# module_RF69.net
KiCad netlist of a schematic drawn in EAGLE
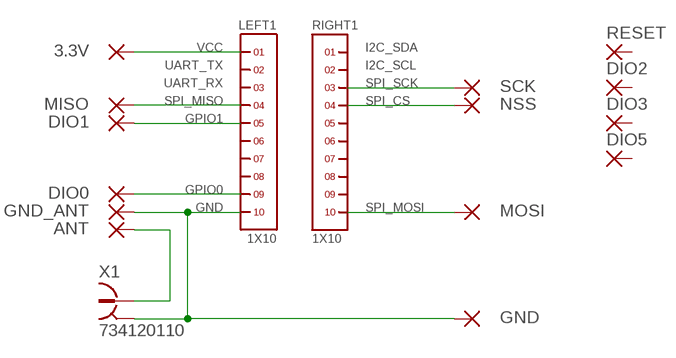
[diagram p0: schematic, sheet 1]

(export (version "E")
  (design (tool "Eeschema 10.0.6"))
  (components
    (comp (ref "3.3V")
      (value "SMD2")
      (footprint "eagle-import:SMD1,27-2,54")
      (libsource (lib "eagle-import") (part "SMD2"))
    )
    (comp (ref "ANT")
      (value "SMD2")
      (footprint "eagle-import:SMD1,27-2,54")
      (libsource (lib "eagle-import") (part "SMD2"))
    )
    (comp (ref "DIO0")
      (value "SMD2")
      (footprint "eagle-import:SMD1,27-2,54")
      (libsource (lib "eagle-import") (part "SMD2"))
    )
    (comp (ref "DIO1")
      (value "SMD2")
      (footprint "eagle-import:SMD1,27-2,54")
      (libsource (lib "eagle-import") (part "SMD2"))
    )
    (comp (ref "DIO2")
      (value "SMD2")
      (footprint "eagle-import:SMD1,27-2,54")
      (libsource (lib "eagle-import") (part "SMD2"))
    )
    (comp (ref "DIO3")
      (value "SMD2")
      (footprint "eagle-import:SMD1,27-2,54")
      (libsource (lib "eagle-import") (part "SMD2"))
    )
    (comp (ref "DIO5")
      (value "SMD2")
      (footprint "eagle-import:SMD1,27-2,54")
      (libsource (lib "eagle-import") (part "SMD2"))
    )
    (comp (ref "GND")
      (value "SMD2")
      (footprint "eagle-import:SMD1,27-2,54")
      (libsource (lib "eagle-import") (part "SMD2"))
    )
    (comp (ref "GND_ANT")
      (value "SMD2")
      (footprint "eagle-import:SMD1,27-2,54")
      (libsource (lib "eagle-import") (part "SMD2"))
    )
    (comp (ref "LEFT1")
      (value "1X10")
      (footprint "eagle-import:1X10")
      (libsource (lib "eagle-import") (part "1X10"))
    )
    (comp (ref "MISO")
      (value "SMD2")
      (footprint "eagle-import:SMD1,27-2,54")
      (libsource (lib "eagle-import") (part "SMD2"))
    )
    (comp (ref "MOSI")
      (value "SMD2")
      (footprint "eagle-import:SMD1,27-2,54")
      (libsource (lib "eagle-import") (part "SMD2"))
    )
    (comp (ref "NSS")
      (value "SMD2")
      (footprint "eagle-import:SMD1,27-2,54")
      (libsource (lib "eagle-import") (part "SMD2"))
    )
    (comp (ref "RESET")
      (value "SMD2")
      (footprint "eagle-import:SMD1,27-2,54")
      (libsource (lib "eagle-import") (part "SMD2"))
    )
    (comp (ref "RIGHT1")
      (value "1X10")
      (footprint "eagle-import:1X10")
      (libsource (lib "eagle-import") (part "1X10"))
    )
    (comp (ref "SCK")
      (value "SMD2")
      (footprint "eagle-import:SMD1,27-2,54")
      (libsource (lib "eagle-import") (part "SMD2"))
    )
    (comp (ref "X1")
      (value "734120110")
      (footprint "eagle-import:734120110")
      (libsource (lib "eagle-import") (part "734120110"))
    )
  )
  (nets
    (net (code "1") (name "Net-(3.3V-P)") (class "Default")
      (node (ref "3.3V") (pin "1") (pinfunction "P_1") (pintype "passive"))
      (node (ref "LEFT1") (pin "1") (pinfunction "1_1") (pintype "bidirectional"))
    )
    (net (code "2") (name "Net-(ANT-P)") (class "Default")
      (node (ref "ANT") (pin "1") (pinfunction "P_1") (pintype "passive"))
      (node (ref "X1") (pin "1") (pinfunction "1_1") (pintype "passive"))
    )
    (net (code "3") (name "Net-(DIO0-P)") (class "Default")
      (node (ref "DIO0") (pin "1") (pinfunction "P_1") (pintype "passive"))
      (node (ref "LEFT1") (pin "9") (pinfunction "9_9") (pintype "bidirectional"))
    )
    (net (code "4") (name "Net-(DIO1-P)") (class "Default")
      (node (ref "DIO1") (pin "1") (pinfunction "P_1") (pintype "passive"))
      (node (ref "LEFT1") (pin "5") (pinfunction "5_5") (pintype "bidirectional"))
    )
    (net (code "5") (name "Net-(GND-P)") (class "Default")
      (node (ref "GND") (pin "1") (pinfunction "P_1") (pintype "passive"))
      (node (ref "GND_ANT") (pin "1") (pinfunction "P_1") (pintype "passive"))
      (node (ref "LEFT1") (pin "10") (pinfunction "10_10") (pintype "bidirectional"))
      (node (ref "X1") (pin "S@1") (pinfunction "2_S@1") (pintype "passive"))
      (node (ref "X1") (pin "S@2") (pinfunction "2_S@2") (pintype "passive"))
      (node (ref "X1") (pin "S@3") (pinfunction "2_S@3") (pintype "passive"))
    )
    (net (code "6") (name "Net-(MISO-P)") (class "Default")
      (node (ref "LEFT1") (pin "4") (pinfunction "4_4") (pintype "bidirectional"))
      (node (ref "MISO") (pin "1") (pinfunction "P_1") (pintype "passive"))
    )
    (net (code "7") (name "Net-(MOSI-P)") (class "Default")
      (node (ref "MOSI") (pin "1") (pinfunction "P_1") (pintype "passive"))
      (node (ref "RIGHT1") (pin "10") (pinfunction "10_10") (pintype "bidirectional"))
    )
    (net (code "8") (name "Net-(NSS-P)") (class "Default")
      (node (ref "NSS") (pin "1") (pinfunction "P_1") (pintype "passive"))
      (node (ref "RIGHT1") (pin "4") (pinfunction "4_4") (pintype "bidirectional"))
    )
    (net (code "9") (name "Net-(SCK-P)") (class "Default")
      (node (ref "RIGHT1") (pin "3") (pinfunction "3_3") (pintype "bidirectional"))
      (node (ref "SCK") (pin "1") (pinfunction "P_1") (pintype "passive"))
    )
    (net (code "10") (name "unconnected-(DIO2-P-Pad1)") (class "Default")
      (node (ref "DIO2") (pin "1") (pinfunction "P_1") (pintype "passive"))
    )
    (net (code "11") (name "unconnected-(DIO3-P-Pad1)") (class "Default")
      (node (ref "DIO3") (pin "1") (pinfunction "P_1") (pintype "passive"))
    )
    (net (code "12") (name "unconnected-(DIO5-P-Pad1)") (class "Default")
      (node (ref "DIO5") (pin "1") (pinfunction "P_1") (pintype "passive"))
    )
    (net (code "13") (name "unconnected-(LEFT1-Pad2)") (class "Default")
      (node (ref "LEFT1") (pin "2") (pinfunction "2_2") (pintype "bidirectional"))
    )
    (net (code "14") (name "unconnected-(LEFT1-Pad3)") (class "Default")
      (node (ref "LEFT1") (pin "3") (pinfunction "3_3") (pintype "bidirectional"))
    )
    (net (code "15") (name "unconnected-(LEFT1-Pad6)") (class "Default")
      (node (ref "LEFT1") (pin "6") (pinfunction "6_6") (pintype "bidirectional"))
    )
    (net (code "16") (name "unconnected-(LEFT1-Pad7)") (class "Default")
      (node (ref "LEFT1") (pin "7") (pinfunction "7_7") (pintype "bidirectional"))
    )
    (net (code "17") (name "unconnected-(LEFT1-Pad8)") (class "Default")
      (node (ref "LEFT1") (pin "8") (pinfunction "8_8") (pintype "bidirectional"))
    )
    (net (code "18") (name "unconnected-(RESET-P-Pad1)") (class "Default")
      (node (ref "RESET") (pin "1") (pinfunction "P_1") (pintype "passive"))
    )
    (net (code "19") (name "unconnected-(RIGHT1-Pad1)") (class "Default")
      (node (ref "RIGHT1") (pin "1") (pinfunction "1_1") (pintype "bidirectional"))
    )
    (net (code "20") (name "unconnected-(RIGHT1-Pad2)") (class "Default")
      (node (ref "RIGHT1") (pin "2") (pinfunction "2_2") (pintype "bidirectional"))
    )
    (net (code "21") (name "unconnected-(RIGHT1-Pad5)") (class "Default")
      (node (ref "RIGHT1") (pin "5") (pinfunction "5_5") (pintype "bidirectional"))
    )
    (net (code "22") (name "unconnected-(RIGHT1-Pad6)") (class "Default")
      (node (ref "RIGHT1") (pin "6") (pinfunction "6_6") (pintype "bidirectional"))
    )
    (net (code "23") (name "unconnected-(RIGHT1-Pad7)") (class "Default")
      (node (ref "RIGHT1") (pin "7") (pinfunction "7_7") (pintype "bidirectional"))
    )
    (net (code "24") (name "unconnected-(RIGHT1-Pad8)") (class "Default")
      (node (ref "RIGHT1") (pin "8") (pinfunction "8_8") (pintype "bidirectional"))
    )
    (net (code "25") (name "unconnected-(RIGHT1-Pad9)") (class "Default")
      (node (ref "RIGHT1") (pin "9") (pinfunction "9_9") (pintype "bidirectional"))
    )
  )
)
